# DRV8350R_Schematic.net
KiCad netlist of a schematic drawn in Altium Designer
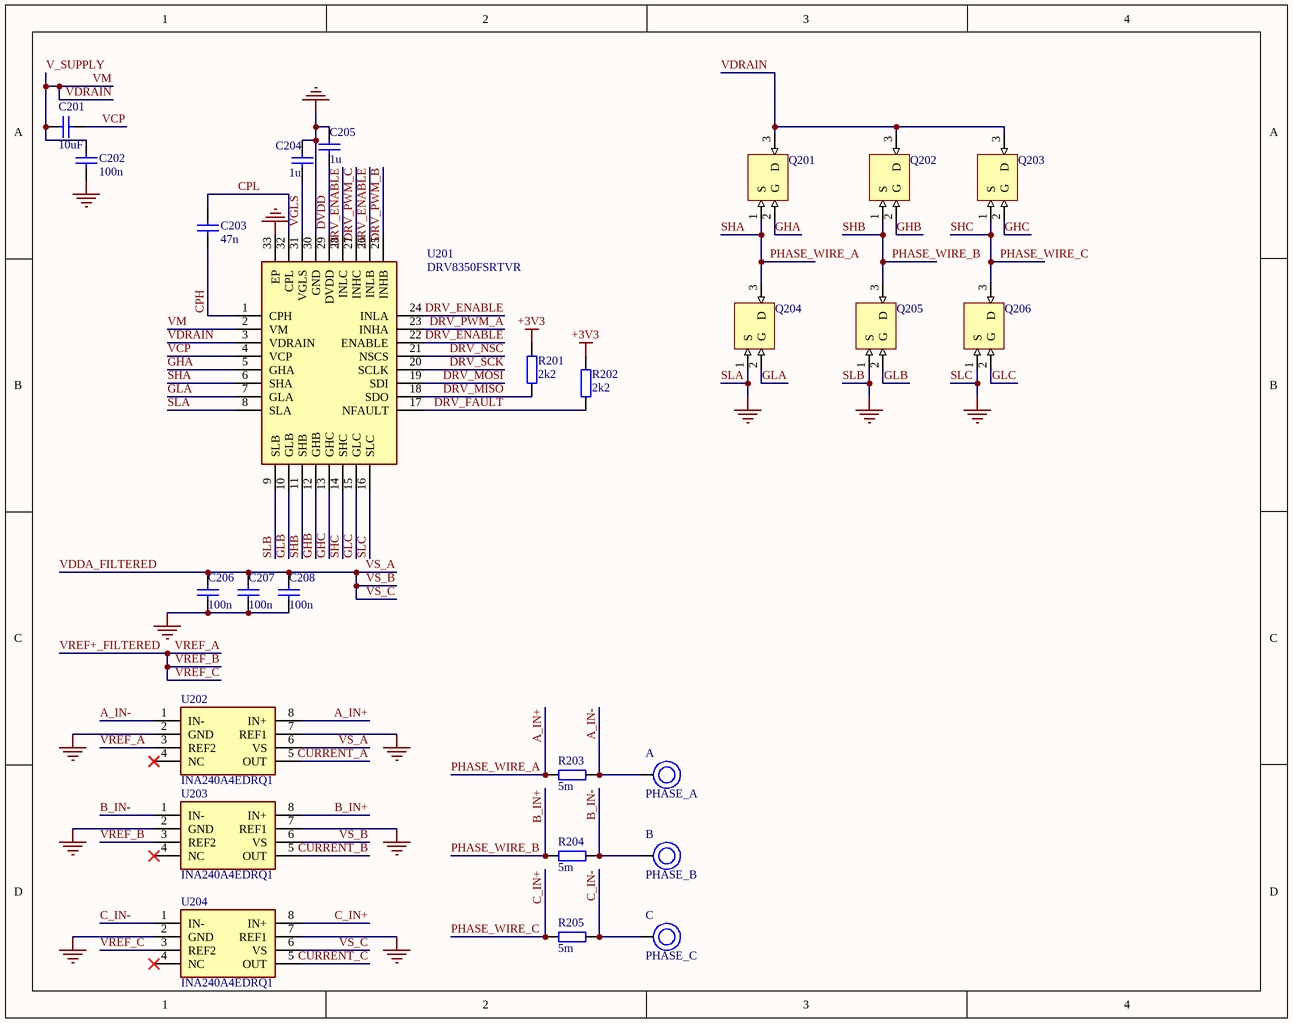
[diagram p0: DRV8350R Schematic.SchDoc]

(export (version "E")
  (design (tool "Eeschema 10.0.6"))
  (components
    (comp (ref "A")
      (value "PHASE_A")
      (footprint "FootprintLib:PAD_HOLE")
      (libsource (lib "SymbolLib") (part "3MM_PAD"))
    )
    (comp (ref "B")
      (value "PHASE_B")
      (footprint "FootprintLib:PAD_HOLE")
      (libsource (lib "SymbolLib") (part "3MM_PAD"))
    )
    (comp (ref "C")
      (value "PHASE_C")
      (footprint "FootprintLib:PAD_HOLE")
      (libsource (lib "SymbolLib") (part "3MM_PAD"))
    )
    (comp (ref "C201")
      (value "10uF")
      (footprint "FootprintLib:CAPC1608X90N")
      (description "Capacitor")
      (fields
        (field (name "MANUFACTURER_PART_NUMBER") "CL05B104KO5NNNC")
        (field (name "MOUSER PART NUMBER") "187-CL05B104KO5NNNC")
      )
      (libsource (lib "SymbolLib") (part "CAP_0805_50V"))
    )
    (comp (ref "C202")
      (value "100n")
      (footprint "FootprintLib:CAPC1608X90N")
      (description "Capacitor")
      (fields
        (field (name "MANUFACTURER_PART_NUMBER") "CL05B104KO5NNNC")
        (field (name "MOUSER PART NUMBER") "187-CL05B104KO5NNNC")
      )
      (libsource (lib "SymbolLib") (part "CAP_0603_100V"))
    )
    (comp (ref "C203")
      (value "47n")
      (footprint "FootprintLib:CAPC1005X55N")
      (description "Capacitor")
      (fields
        (field (name "MANUFACTURER_PART_NUMBER") "CL05B104KO5NNNC")
        (field (name "MOUSER PART NUMBER") "187-CL05B104KO5NNNC")
      )
      (libsource (lib "SymbolLib") (part "CAP_0402_50V"))
    )
    (comp (ref "C204")
      (value "1u")
      (footprint "FootprintLib:CAPC1005X55N")
      (description "Capacitor")
      (fields
        (field (name "MANUFACTURER_PART_NUMBER") "CL05B104KO5NNNC")
        (field (name "MOUSER PART NUMBER") "187-CL05B104KO5NNNC")
      )
      (libsource (lib "SymbolLib") (part "CAP_0402_50V"))
    )
    (comp (ref "C205")
      (value "1u")
      (footprint "FootprintLib:CAPC1005X55N")
      (description "Capacitor")
      (fields
        (field (name "MANUFACTURER_PART_NUMBER") "CL05B104KO5NNNC")
        (field (name "MOUSER PART NUMBER") "187-CL05B104KO5NNNC")
      )
      (libsource (lib "SymbolLib") (part "CAP_0402_50V"))
    )
    (comp (ref "C206")
      (value "100n")
      (footprint "CAPC1050X55X23ML05T13")
      (description "Chip Capacitor, 100 nF, +/- 10%, 16 V, -55 to 125 degC, 0402 (1005 Metric), RoHS, Tape and Reel")
      (fields (field (name "MANUFACTURER") "Samsung Electro-Mechanics"))
      (libsource (lib "Altium Content Vault") (part "CAP-NP-2"))
    )
    (comp (ref "C207")
      (value "100n")
      (footprint "CAPC1050X55X23ML05T13")
      (description "Chip Capacitor, 100 nF, +/- 10%, 16 V, -55 to 125 degC, 0402 (1005 Metric), RoHS, Tape and Reel")
      (fields (field (name "MANUFACTURER") "Samsung Electro-Mechanics"))
      (libsource (lib "Altium Content Vault") (part "CAP-NP-2"))
    )
    (comp (ref "C208")
      (value "100n")
      (footprint "CAPC1050X55X23ML05T13")
      (description "Chip Capacitor, 100 nF, +/- 10%, 16 V, -55 to 125 degC, 0402 (1005 Metric), RoHS, Tape and Reel")
      (fields (field (name "MANUFACTURER") "Samsung Electro-Mechanics"))
      (libsource (lib "Altium Content Vault") (part "CAP-NP-2"))
    )
    (comp (ref "Q201")
      (value "NTTFS3D7N06HLTWG")
      (footprint "PQFN-8")
      (libsource (lib "SymbolLib") (part "NTTFS3D7N06HLTWG"))
    )
    (comp (ref "Q202")
      (value "NTTFS3D7N06HLTWG")
      (footprint "PQFN-8")
      (libsource (lib "SymbolLib") (part "NTTFS3D7N06HLTWG"))
    )
    (comp (ref "Q203")
      (value "NTTFS3D7N06HLTWG")
      (footprint "PQFN-8")
      (libsource (lib "SymbolLib") (part "NTTFS3D7N06HLTWG"))
    )
    (comp (ref "Q204")
      (value "NTTFS3D7N06HLTWG")
      (footprint "PQFN-8")
      (libsource (lib "SymbolLib") (part "NTTFS3D7N06HLTWG"))
    )
    (comp (ref "Q205")
      (value "NTTFS3D7N06HLTWG")
      (footprint "PQFN-8")
      (libsource (lib "SymbolLib") (part "NTTFS3D7N06HLTWG"))
    )
    (comp (ref "Q206")
      (value "NTTFS3D7N06HLTWG")
      (footprint "PQFN-8")
      (libsource (lib "SymbolLib") (part "NTTFS3D7N06HLTWG"))
    )
    (comp (ref "R201")
      (value "2k2")
      (footprint "RESC1608X55N")
      (libsource (lib "SymbolLib") (part "RES_0603"))
    )
    (comp (ref "R202")
      (value "2k2")
      (footprint "RESC1608X55N")
      (libsource (lib "SymbolLib") (part "RES_0603"))
    )
    (comp (ref "R203")
      (value "5m")
      (footprint "RESC3216X80N")
      (libsource (lib "SymbolLib") (part "RES_1206"))
    )
    (comp (ref "R204")
      (value "5m")
      (footprint "RESC3216X80N")
      (libsource (lib "SymbolLib") (part "RES_1206"))
    )
    (comp (ref "R205")
      (value "5m")
      (footprint "RESC3216X80N")
      (libsource (lib "SymbolLib") (part "RES_1206"))
    )
    (comp (ref "U201")
      (value "DRV8350FSRTVR")
      (footprint "WQFN-N32-THM")
      (libsource (lib "SymbolLib") (part "DRV8350FSRTVR"))
    )
    (comp (ref "U202")
      (value "INA240A4EDRQ1")
      (footprint "SamacSys:SOIC127P600X175-8N")
      (description "Integrated Circuit")
      (fields (field (name "MOUSER PART NUMBER") "595-INA240A4EDRQ1"))
      (libsource (lib "*") (part "INA240A4EDRQ1"))
    )
    (comp (ref "U203")
      (value "INA240A4EDRQ1")
      (footprint "SamacSys:SOIC127P600X175-8N")
      (description "Integrated Circuit")
      (fields (field (name "MOUSER PART NUMBER") "595-INA240A4EDRQ1"))
      (libsource (lib "*") (part "INA240A4EDRQ1"))
    )
    (comp (ref "U204")
      (value "INA240A4EDRQ1")
      (footprint "SamacSys:SOIC127P600X175-8N")
      (description "Integrated Circuit")
      (fields (field (name "MOUSER PART NUMBER") "595-INA240A4EDRQ1"))
      (libsource (lib "*") (part "INA240A4EDRQ1"))
    )
  )
  (nets
    (net (code "1") (name "+3V3") (class "Default")
      (node (ref "R201") (pin "2") (pinfunction "2_2") (pintype "passive"))
      (node (ref "R202") (pin "2") (pinfunction "2_2") (pintype "passive"))
    )
    (net (code "2") (name "/A_IN+") (class "Default")
      (node (ref "Q201") (pin "1") (pinfunction "S_1") (pintype "input"))
      (node (ref "Q204") (pin "3") (pinfunction "D_3") (pintype "input"))
      (node (ref "R203") (pin "1") (pinfunction "1_1") (pintype "passive"))
      (node (ref "U201") (pin "6") (pinfunction "SHA_6") (pintype "passive"))
      (node (ref "U202") (pin "8") (pinfunction "IN+_8") (pintype "passive"))
    )
    (net (code "3") (name "/A_IN-") (class "Default")
      (node (ref "A") (pin "1") (pinfunction "1_1") (pintype "passive"))
      (node (ref "R203") (pin "2") (pinfunction "2_2") (pintype "passive"))
      (node (ref "U202") (pin "1") (pinfunction "IN-_1") (pintype "passive"))
    )
    (net (code "4") (name "/B_IN+") (class "Default")
      (node (ref "Q202") (pin "1") (pinfunction "S_1") (pintype "input"))
      (node (ref "Q205") (pin "3") (pinfunction "D_3") (pintype "input"))
      (node (ref "R204") (pin "1") (pinfunction "1_1") (pintype "passive"))
      (node (ref "U201") (pin "11") (pinfunction "SHB_11") (pintype "passive"))
      (node (ref "U203") (pin "8") (pinfunction "IN+_8") (pintype "passive"))
    )
    (net (code "5") (name "/B_IN-") (class "Default")
      (node (ref "B") (pin "1") (pinfunction "1_1") (pintype "passive"))
      (node (ref "R204") (pin "2") (pinfunction "2_2") (pintype "passive"))
      (node (ref "U203") (pin "1") (pinfunction "IN-_1") (pintype "passive"))
    )
    (net (code "6") (name "/CPH") (class "Default")
      (node (ref "C203") (pin "2") (pinfunction "2_2") (pintype "passive"))
      (node (ref "U201") (pin "1") (pinfunction "CPH_1") (pintype "passive"))
    )
    (net (code "7") (name "/CPL") (class "Default")
      (node (ref "C203") (pin "1") (pinfunction "1_1") (pintype "passive"))
      (node (ref "U201") (pin "32") (pinfunction "CPL_32") (pintype "passive"))
    )
    (net (code "8") (name "/CURRENT_A") (class "Default")
      (node (ref "U202") (pin "5") (pinfunction "OUT_5") (pintype "passive"))
    )
    (net (code "9") (name "/CURRENT_B") (class "Default")
      (node (ref "U203") (pin "5") (pinfunction "OUT_5") (pintype "passive"))
    )
    (net (code "10") (name "/CURRENT_C") (class "Default")
      (node (ref "U204") (pin "5") (pinfunction "OUT_5") (pintype "passive"))
    )
    (net (code "11") (name "/C_IN+") (class "Default")
      (node (ref "Q203") (pin "1") (pinfunction "S_1") (pintype "input"))
      (node (ref "Q206") (pin "3") (pinfunction "D_3") (pintype "input"))
      (node (ref "R205") (pin "1") (pinfunction "1_1") (pintype "passive"))
      (node (ref "U201") (pin "14") (pinfunction "SHC_14") (pintype "passive"))
      (node (ref "U204") (pin "8") (pinfunction "IN+_8") (pintype "passive"))
    )
    (net (code "12") (name "/C_IN-") (class "Default")
      (node (ref "C") (pin "1") (pinfunction "1_1") (pintype "passive"))
      (node (ref "R205") (pin "2") (pinfunction "2_2") (pintype "passive"))
      (node (ref "U204") (pin "1") (pinfunction "IN-_1") (pintype "passive"))
    )
    (net (code "13") (name "/DRV_ENABLE") (class "Default")
      (node (ref "U201") (pin "22") (pinfunction "ENABLE_22") (pintype "passive"))
      (node (ref "U201") (pin "24") (pinfunction "INLA_24") (pintype "passive"))
      (node (ref "U201") (pin "26") (pinfunction "INLB_26") (pintype "passive"))
      (node (ref "U201") (pin "28") (pinfunction "INLC_28") (pintype "passive"))
    )
    (net (code "14") (name "/DRV_FAULT") (class "Default")
      (node (ref "R202") (pin "1") (pinfunction "1_1") (pintype "passive"))
      (node (ref "U201") (pin "17") (pinfunction "NFAULT_17") (pintype "passive"))
    )
    (net (code "15") (name "/DRV_MISO") (class "Default")
      (node (ref "R201") (pin "1") (pinfunction "1_1") (pintype "passive"))
      (node (ref "U201") (pin "18") (pinfunction "SDO_18") (pintype "passive"))
    )
    (net (code "16") (name "/DRV_MOSI") (class "Default")
      (node (ref "U201") (pin "19") (pinfunction "SDI_19") (pintype "passive"))
    )
    (net (code "17") (name "/DRV_NSC") (class "Default")
      (node (ref "U201") (pin "21") (pinfunction "NSCS_21") (pintype "passive"))
    )
    (net (code "18") (name "/DRV_PWM_A") (class "Default")
      (node (ref "U201") (pin "23") (pinfunction "INHA_23") (pintype "passive"))
    )
    (net (code "19") (name "/DRV_PWM_B") (class "Default")
      (node (ref "U201") (pin "25") (pinfunction "INHB_25") (pintype "passive"))
    )
    (net (code "20") (name "/DRV_PWM_C") (class "Default")
      (node (ref "U201") (pin "27") (pinfunction "INHC_27") (pintype "passive"))
    )
    (net (code "21") (name "/DRV_SCK") (class "Default")
      (node (ref "U201") (pin "20") (pinfunction "SCLK_20") (pintype "passive"))
    )
    (net (code "22") (name "/DVDD") (class "Default")
      (node (ref "C205") (pin "2") (pinfunction "2_2") (pintype "passive"))
      (node (ref "U201") (pin "29") (pinfunction "DVDD_29") (pintype "passive"))
    )
    (net (code "23") (name "/GHA") (class "Default")
      (node (ref "Q201") (pin "2") (pinfunction "G_2") (pintype "input"))
      (node (ref "U201") (pin "5") (pinfunction "GHA_5") (pintype "passive"))
    )
    (net (code "24") (name "/GHB") (class "Default")
      (node (ref "Q202") (pin "2") (pinfunction "G_2") (pintype "input"))
      (node (ref "U201") (pin "12") (pinfunction "GHB_12") (pintype "passive"))
    )
    (net (code "25") (name "/GHC") (class "Default")
      (node (ref "Q203") (pin "2") (pinfunction "G_2") (pintype "input"))
      (node (ref "U201") (pin "13") (pinfunction "GHC_13") (pintype "passive"))
    )
    (net (code "26") (name "/GLA") (class "Default")
      (node (ref "Q204") (pin "2") (pinfunction "G_2") (pintype "input"))
      (node (ref "U201") (pin "7") (pinfunction "GLA_7") (pintype "passive"))
    )
    (net (code "27") (name "/GLB") (class "Default")
      (node (ref "Q205") (pin "2") (pinfunction "G_2") (pintype "input"))
      (node (ref "U201") (pin "10") (pinfunction "GLB_10") (pintype "passive"))
    )
    (net (code "28") (name "/GLC") (class "Default")
      (node (ref "Q206") (pin "2") (pinfunction "G_2") (pintype "input"))
      (node (ref "U201") (pin "15") (pinfunction "GLC_15") (pintype "passive"))
    )
    (net (code "29") (name "/VCP") (class "Default")
      (node (ref "C201") (pin "2") (pinfunction "2_2") (pintype "passive"))
      (node (ref "U201") (pin "4") (pinfunction "VCP_4") (pintype "passive"))
    )
    (net (code "30") (name "/VDDA_FILTERED") (class "Default")
      (node (ref "C206") (pin "2") (pinfunction "2_2") (pintype "passive"))
      (node (ref "C207") (pin "2") (pinfunction "2_2") (pintype "passive"))
      (node (ref "C208") (pin "2") (pinfunction "2_2") (pintype "passive"))
      (node (ref "U202") (pin "6") (pinfunction "VS_6") (pintype "passive"))
      (node (ref "U203") (pin "6") (pinfunction "VS_6") (pintype "passive"))
      (node (ref "U204") (pin "6") (pinfunction "VS_6") (pintype "passive"))
    )
    (net (code "31") (name "/VDRAIN") (class "Default")
      (node (ref "C201") (pin "1") (pinfunction "1_1") (pintype "passive"))
      (node (ref "C202") (pin "2") (pinfunction "2_2") (pintype "passive"))
      (node (ref "Q201") (pin "3") (pinfunction "D_3") (pintype "input"))
      (node (ref "Q202") (pin "3") (pinfunction "D_3") (pintype "input"))
      (node (ref "Q203") (pin "3") (pinfunction "D_3") (pintype "input"))
      (node (ref "U201") (pin "2") (pinfunction "VM_2") (pintype "passive"))
      (node (ref "U201") (pin "3") (pinfunction "VDRAIN_3") (pintype "passive"))
    )
    (net (code "32") (name "/VGLS") (class "Default")
      (node (ref "C204") (pin "1") (pinfunction "1_1") (pintype "passive"))
      (node (ref "U201") (pin "31") (pinfunction "VGLS_31") (pintype "passive"))
    )
    (net (code "33") (name "/VREF+_FILTERED") (class "Default")
      (node (ref "U202") (pin "3") (pinfunction "REF2_3") (pintype "passive"))
      (node (ref "U203") (pin "3") (pinfunction "REF2_3") (pintype "passive"))
      (node (ref "U204") (pin "3") (pinfunction "REF2_3") (pintype "passive"))
    )
    (net (code "34") (name "GND") (class "Default")
      (node (ref "C202") (pin "1") (pinfunction "1_1") (pintype "passive"))
      (node (ref "C204") (pin "2") (pinfunction "2_2") (pintype "passive"))
      (node (ref "C205") (pin "1") (pinfunction "1_1") (pintype "passive"))
      (node (ref "C206") (pin "1") (pinfunction "1_1") (pintype "passive"))
      (node (ref "C207") (pin "1") (pinfunction "1_1") (pintype "passive"))
      (node (ref "C208") (pin "1") (pinfunction "1_1") (pintype "passive"))
      (node (ref "Q204") (pin "1") (pinfunction "S_1") (pintype "input"))
      (node (ref "Q205") (pin "1") (pinfunction "S_1") (pintype "input"))
      (node (ref "Q206") (pin "1") (pinfunction "S_1") (pintype "input"))
      (node (ref "U201") (pin "16") (pinfunction "SLC_16") (pintype "passive"))
      (node (ref "U201") (pin "30") (pinfunction "GND_30") (pintype "passive"))
      (node (ref "U201") (pin "33") (pinfunction "EP_33") (pintype "passive"))
      (node (ref "U201") (pin "8") (pinfunction "SLA_8") (pintype "passive"))
      (node (ref "U201") (pin "9") (pinfunction "SLB_9") (pintype "passive"))
      (node (ref "U202") (pin "2") (pinfunction "GND_2") (pintype "passive"))
      (node (ref "U202") (pin "7") (pinfunction "REF1_7") (pintype "passive"))
      (node (ref "U203") (pin "2") (pinfunction "GND_2") (pintype "passive"))
      (node (ref "U203") (pin "7") (pinfunction "REF1_7") (pintype "passive"))
      (node (ref "U204") (pin "2") (pinfunction "GND_2") (pintype "passive"))
      (node (ref "U204") (pin "7") (pinfunction "REF1_7") (pintype "passive"))
    )
    (net (code "35") (name "unconnected-(U202-NC-Pad4)") (class "Default")
      (node (ref "U202") (pin "4") (pinfunction "NC_4") (pintype "passive+no_connect"))
    )
    (net (code "36") (name "unconnected-(U203-NC-Pad4)") (class "Default")
      (node (ref "U203") (pin "4") (pinfunction "NC_4") (pintype "passive+no_connect"))
    )
    (net (code "37") (name "unconnected-(U204-NC-Pad4)") (class "Default")
      (node (ref "U204") (pin "4") (pinfunction "NC_4") (pintype "passive+no_connect"))
    )
  )
)
